# PK_MUV_L2.net
KiCad netlist of a schematic drawn in EAGLE
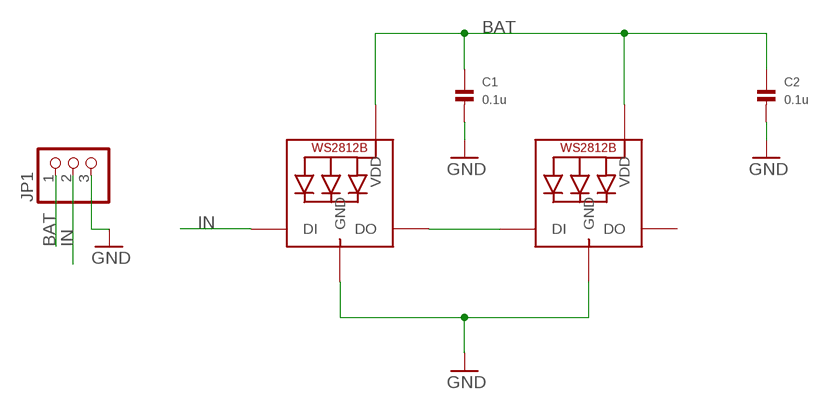
[diagram p0: schematic, sheet 1]

(export (version "E")
  (design (tool "Eeschema 10.0.6"))
  (components
    (comp (ref "C1")
      (value "0.1u")
      (footprint "eagle-import:1206")
      (libsource (lib "eagle-import") (part "CAP_CERAMIC1206"))
    )
    (comp (ref "C2")
      (value "0.1u")
      (footprint "eagle-import:1206")
      (libsource (lib "eagle-import") (part "CAP_CERAMIC1206"))
    )
    (comp (ref "JP1")
      (value "HEADER-1X3")
      (footprint "eagle-import:1X03_OVAL")
      (libsource (lib "eagle-import") (part "HEADER-1X3"))
    )
    (comp (ref "LED1")
      (value "WS2812B_5050N")
      (footprint "eagle-import:WS2812B-NARROW")
      (libsource (lib "eagle-import") (part "WS2812B_5050N"))
    )
    (comp (ref "LED2")
      (value "WS2812B_5050N")
      (footprint "eagle-import:WS2812B-NARROW")
      (libsource (lib "eagle-import") (part "WS2812B_5050N"))
    )
  )
  (nets
    (net (code "1") (name "/BAT") (class "Default")
      (node (ref "C1") (pin "1") (pinfunction "P$1_1") (pintype "passive"))
      (node (ref "C2") (pin "1") (pinfunction "P$1_1") (pintype "passive"))
      (node (ref "JP1") (pin "1") (pinfunction "1_1") (pintype "passive"))
      (node (ref "LED1") (pin "1-VDD") (pinfunction "VDD_1-VDD") (pintype "power_in"))
      (node (ref "LED2") (pin "1-VDD") (pinfunction "VDD_1-VDD") (pintype "power_in"))
    )
    (net (code "2") (name "/IN") (class "Default")
      (node (ref "JP1") (pin "2") (pinfunction "2_2") (pintype "passive"))
      (node (ref "LED1") (pin "4-DIN") (pinfunction "DI_4-DIN") (pintype "input"))
    )
    (net (code "3") (name "GND") (class "Default")
      (node (ref "C1") (pin "2") (pinfunction "P$2_2") (pintype "passive"))
      (node (ref "C2") (pin "2") (pinfunction "P$2_2") (pintype "passive"))
      (node (ref "JP1") (pin "3") (pinfunction "3_3") (pintype "passive"))
      (node (ref "LED1") (pin "3-GND") (pinfunction "GND_3-GND") (pintype "power_in"))
      (node (ref "LED2") (pin "3-GND") (pinfunction "GND_3-GND") (pintype "power_in"))
    )
    (net (code "4") (name "Net-(LED1-DO)") (class "Default")
      (node (ref "LED1") (pin "2-DOUT") (pinfunction "DO_2-DOUT") (pintype "output"))
      (node (ref "LED2") (pin "4-DIN") (pinfunction "DI_4-DIN") (pintype "input"))
    )
    (net (code "5") (name "unconnected-(LED2-DO-Pad2-DOUT)") (class "Default")
      (node (ref "LED2") (pin "2-DOUT") (pinfunction "DO_2-DOUT") (pintype "output"))
    )
  )
)
